# mainboard_rs485_v1_5.net
KiCad netlist of a schematic drawn in Altium Designer
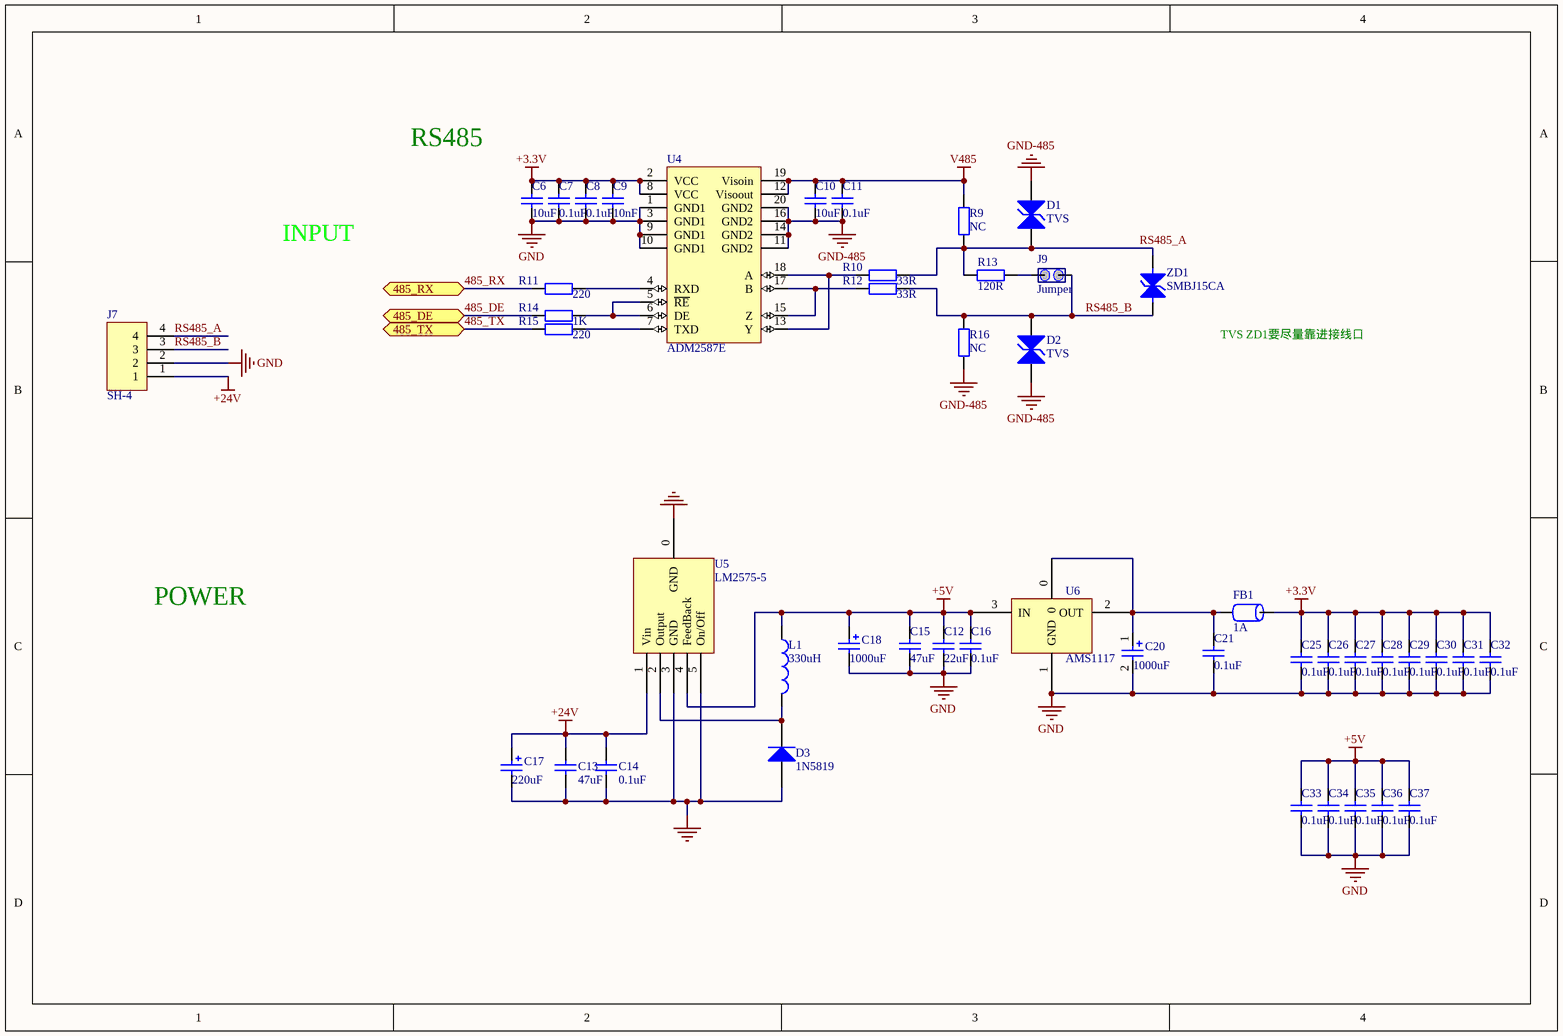
[diagram p0: mainboard_rs485.v1.5.SchDoc]

(export (version "E")
  (design (tool "Eeschema 10.0.6"))
  (components
    (comp (ref "C6")
      (value "10uF")
      (footprint "0805")
      (description "Capacitor")
      (fields (field (name "PUBLISHER") "Altium Limited"))
      (libsource (lib "TIAN's Schlib") (part "Cap"))
    )
    (comp (ref "C7")
      (value "0.1uF")
      (footprint "0805")
      (description "Capacitor")
      (fields (field (name "PUBLISHER") "Altium Limited"))
      (libsource (lib "TIAN's Schlib") (part "Cap"))
    )
    (comp (ref "C8")
      (value "0.1uF")
      (footprint "0805")
      (description "Capacitor")
      (fields (field (name "PUBLISHER") "Altium Limited"))
      (libsource (lib "TIAN's Schlib") (part "Cap"))
    )
    (comp (ref "C9")
      (value "10nF")
      (footprint "0805")
      (description "Capacitor")
      (fields (field (name "PUBLISHER") "Altium Limited"))
      (libsource (lib "TIAN's Schlib") (part "Cap"))
    )
    (comp (ref "C10")
      (value "10uF")
      (footprint "0805")
      (description "Capacitor")
      (fields (field (name "PUBLISHER") "Altium Limited"))
      (libsource (lib "TIAN's Schlib") (part "Cap"))
    )
    (comp (ref "C11")
      (value "0.1uF")
      (footprint "0805")
      (description "Capacitor")
      (fields (field (name "PUBLISHER") "Altium Limited"))
      (libsource (lib "TIAN's Schlib") (part "Cap"))
    )
    (comp (ref "C12") (value "22uF") (footprint "1206") (libsource (lib "Componet") (part "Cap0805")))
    (comp (ref "C13")
      (value "47uF")
      (footprint "1812")
      (description "Capacitor")
      (fields (field (name "PUBLISHER") "Altium Limited"))
      (libsource (lib "Miscellaneous Devices") (part "Cap"))
    )
    (comp (ref "C14")
      (value "0.1uF")
      (footprint "0805")
      (description "Capacitor")
      (fields (field (name "PUBLISHER") "Altium Limited"))
      (libsource (lib "Miscellaneous Devices") (part "Cap"))
    )
    (comp (ref "C15") (value "47uF") (footprint "1812") (libsource (lib "Componet") (part "Cap0805")))
    (comp (ref "C16") (value "0.1uF") (footprint "0805") (libsource (lib "Componet") (part "Cap0805")))
    (comp (ref "C17")
      (value "220uF")
      (footprint "CAP-5mm")
      (description "Polarized Capacitor (Radial)")
      (fields (field (name "PUBLISHER") "Altium Limited"))
      (libsource (lib "Miscellaneous Devices") (part "Cap Pol1"))
    )
    (comp (ref "C18")
      (value "1000uF")
      (footprint "CAP_SMT_10X10")
      (description "Polarized Capacitor (Radial)")
      (fields (field (name "PUBLISHER") "Altium Limited"))
      (libsource (lib "Miscellaneous Devices") (part "Cap Pol1"))
    )
    (comp (ref "C20")
      (value "1000uF")
      (footprint "CAP_SMT_10X10")
      (description "Polarized Capacitor (Radial)")
      (fields (field (name "PUBLISHER") "Altium Limited"))
      (libsource (lib "") (part "Cap Pol1_1"))
    )
    (comp (ref "C21") (value "0.1uF") (footprint "0805") (libsource (lib "Componet") (part "Cap0805")))
    (comp (ref "C25") (value "0.1uF") (footprint "0805") (libsource (lib "Componet") (part "Cap0805")))
    (comp (ref "C26") (value "0.1uF") (footprint "0805") (libsource (lib "Componet") (part "Cap0805")))
    (comp (ref "C27") (value "0.1uF") (footprint "0805") (libsource (lib "Componet") (part "Cap0805")))
    (comp (ref "C28") (value "0.1uF") (footprint "0805") (libsource (lib "Componet") (part "Cap0805")))
    (comp (ref "C29") (value "0.1uF") (footprint "0805") (libsource (lib "Componet") (part "Cap0805")))
    (comp (ref "C30") (value "0.1uF") (footprint "0805") (libsource (lib "Componet") (part "Cap0805")))
    (comp (ref "C31") (value "0.1uF") (footprint "0805") (libsource (lib "Componet") (part "Cap0805")))
    (comp (ref "C32") (value "0.1uF") (footprint "0805") (libsource (lib "Componet") (part "Cap0805")))
    (comp (ref "C33") (value "0.1uF") (footprint "0805") (libsource (lib "Componet") (part "Cap0805")))
    (comp (ref "C34") (value "0.1uF") (footprint "0805") (libsource (lib "Componet") (part "Cap0805")))
    (comp (ref "C35") (value "0.1uF") (footprint "0805") (libsource (lib "Componet") (part "Cap0805")))
    (comp (ref "C36") (value "0.1uF") (footprint "0805") (libsource (lib "Componet") (part "Cap0805")))
    (comp (ref "C37") (value "0.1uF") (footprint "0805") (libsource (lib "Componet") (part "Cap0805")))
    (comp (ref "D1")
      (value "TVS")
      (footprint "SMBJ_DO-214")
      (fields (field (name "PUBLISHER") "Altium Limited"))
      (libsource (lib "TIAN's Schlib") (part "TVS"))
    )
    (comp (ref "D2")
      (value "TVS")
      (footprint "SMBJ_DO-214")
      (fields (field (name "PUBLISHER") "Altium Limited"))
      (libsource (lib "TIAN's Schlib") (part "TVS"))
    )
    (comp (ref "D3")
      (value "1N5819")
      (footprint "Diode_TP2")
      (description "High Conductance Fast Diode")
      (fields (field (name "PUBLISHER") "Altium Limited"))
      (libsource (lib "Miscellaneous Devices") (part "Diode 1N4148"))
    )
    (comp (ref "FB1") (value "1A") (footprint "0805") (libsource (lib "Connector") (part "FERRITE")))
    (comp (ref "J7") (value "SH-4") (footprint "PWR") (libsource (lib "Connector") (part "SH-4")))
    (comp (ref "J9") (value "Jumper") (footprint "J254-2") (libsource (lib "Connector") (part "Jumper")))
    (comp (ref "L1")
      (value "330uH")
      (footprint "Inductance")
      (description "Inductor")
      (fields (field (name "PUBLISHER") "Altium Limited"))
      (libsource (lib "Miscellaneous Devices") (part "Inductor"))
    )
    (comp (ref "R9")
      (value "NC")
      (footprint "0805")
      (description "Resistor")
      (fields (field (name "PUBLISHER") "Altium Limited"))
      (libsource (lib "TIAN's Schlib") (part "Res2"))
    )
    (comp (ref "R10")
      (value "33R")
      (footprint "0805")
      (description "Resistor")
      (fields (field (name "PUBLISHER") "Altium Limited"))
      (libsource (lib "") (part "Res2_2"))
    )
    (comp (ref "R11")
      (value "220")
      (footprint "0805")
      (description "Resistor")
      (fields (field (name "PUBLISHER") "Altium Limited"))
      (libsource (lib "TIAN's Schlib") (part "Res2"))
    )
    (comp (ref "R12")
      (value "33R")
      (footprint "0805")
      (description "Resistor")
      (fields (field (name "PUBLISHER") "Altium Limited"))
      (libsource (lib "") (part "Res2_2"))
    )
    (comp (ref "R13")
      (value "120R")
      (footprint "0805")
      (description "Resistor")
      (fields (field (name "PUBLISHER") "Altium Limited"))
      (libsource (lib "") (part "Res2_1"))
    )
    (comp (ref "R14")
      (value "1K")
      (footprint "0805")
      (description "Resistor")
      (fields (field (name "PUBLISHER") "Altium Limited"))
      (libsource (lib "TIAN's Schlib") (part "Res2"))
    )
    (comp (ref "R15")
      (value "220")
      (footprint "0805")
      (description "Resistor")
      (fields (field (name "PUBLISHER") "Altium Limited"))
      (libsource (lib "TIAN's Schlib") (part "Res2"))
    )
    (comp (ref "R16")
      (value "NC")
      (footprint "0805")
      (description "Resistor")
      (fields (field (name "PUBLISHER") "Altium Limited"))
      (libsource (lib "TIAN's Schlib") (part "Res2"))
    )
    (comp (ref "U4")
      (value "ADM2587E")
      (footprint "SOIC_W_20")
      (description "isolated DC-DC RS485")
      (libsource (lib "TIAN's Schlib") (part "ADM2587E"))
    )
    (comp (ref "U5") (value "LM2575-5") (footprint "TO-263") (libsource (lib "Leon") (part "LM25XX")))
    (comp (ref "U6") (value "AMS1117") (footprint "TO-223") (libsource (lib "Chip") (part "AMS1117")))
    (comp (ref "ZD1")
      (value "SMBJ15CA")
      (footprint "DO-214AA/SMB")
      (description "瞬态抑制二极管")
      (libsource (lib "ALARM") (part "TVS"))
    )
  )
  (nets
    (net (code "1") (name "+3.3V") (class "Default")
      (node (ref "C25") (pin "2") (pinfunction "2_2") (pintype "passive"))
      (node (ref "C26") (pin "2") (pinfunction "2_2") (pintype "passive"))
      (node (ref "C27") (pin "2") (pinfunction "2_2") (pintype "passive"))
      (node (ref "C28") (pin "2") (pinfunction "2_2") (pintype "passive"))
      (node (ref "C29") (pin "2") (pinfunction "2_2") (pintype "passive"))
      (node (ref "C30") (pin "2") (pinfunction "2_2") (pintype "passive"))
      (node (ref "C31") (pin "2") (pinfunction "2_2") (pintype "passive"))
      (node (ref "C32") (pin "2") (pinfunction "2_2") (pintype "passive"))
      (node (ref "C6") (pin "2") (pinfunction "2_2") (pintype "passive"))
      (node (ref "C7") (pin "2") (pinfunction "2_2") (pintype "passive"))
      (node (ref "C8") (pin "2") (pinfunction "2_2") (pintype "passive"))
      (node (ref "C9") (pin "2") (pinfunction "2_2") (pintype "passive"))
      (node (ref "FB1") (pin "2") (pinfunction "2_2") (pintype "passive"))
      (node (ref "U4") (pin "2") (pinfunction "VCC_2") (pintype "passive"))
      (node (ref "U4") (pin "8") (pinfunction "VCC_8") (pintype "passive"))
    )
    (net (code "2") (name "+5V") (class "Default")
      (node (ref "C12") (pin "2") (pinfunction "2_2") (pintype "passive"))
      (node (ref "C15") (pin "2") (pinfunction "2_2") (pintype "passive"))
      (node (ref "C16") (pin "2") (pinfunction "2_2") (pintype "passive"))
      (node (ref "C18") (pin "1") (pinfunction "1_1") (pintype "passive"))
      (node (ref "C33") (pin "2") (pinfunction "2_2") (pintype "passive"))
      (node (ref "C34") (pin "2") (pinfunction "2_2") (pintype "passive"))
      (node (ref "C35") (pin "2") (pinfunction "2_2") (pintype "passive"))
      (node (ref "C36") (pin "2") (pinfunction "2_2") (pintype "passive"))
      (node (ref "C37") (pin "2") (pinfunction "2_2") (pintype "passive"))
      (node (ref "L1") (pin "1") (pinfunction "1_1") (pintype "passive"))
      (node (ref "U5") (pin "4") (pinfunction "FeedBack_4") (pintype "passive"))
      (node (ref "U6") (pin "3") (pinfunction "IN_3") (pintype "passive"))
    )
    (net (code "3") (name "+24V") (class "Default")
      (node (ref "C13") (pin "2") (pinfunction "2_2") (pintype "passive"))
      (node (ref "C14") (pin "2") (pinfunction "2_2") (pintype "passive"))
      (node (ref "C17") (pin "1") (pinfunction "1_1") (pintype "passive"))
      (node (ref "J7") (pin "1") (pinfunction "1_1") (pintype "passive"))
      (node (ref "U5") (pin "1") (pinfunction "Vin_1") (pintype "passive"))
    )
    (net (code "4") (name "/485_DE") (class "Default")
      (node (ref "R14") (pin "1") (pinfunction "1_1") (pintype "passive"))
    )
    (net (code "5") (name "/485_RX") (class "Default")
      (node (ref "R11") (pin "1") (pinfunction "1_1") (pintype "passive"))
    )
    (net (code "6") (name "/485_TX") (class "Default")
      (node (ref "R15") (pin "1") (pinfunction "1_1") (pintype "passive"))
    )
    (net (code "7") (name "/RS485_A") (class "Default")
      (node (ref "D1") (pin "2") (pinfunction "K_2") (pintype "passive"))
      (node (ref "J7") (pin "4") (pinfunction "4_4") (pintype "passive"))
      (node (ref "R10") (pin "2") (pinfunction "2_2") (pintype "passive"))
      (node (ref "R13") (pin "2") (pinfunction "2_2") (pintype "passive"))
      (node (ref "R9") (pin "1") (pinfunction "1_1") (pintype "passive"))
      (node (ref "ZD1") (pin "1") (pinfunction "1_1") (pintype "passive"))
    )
    (net (code "8") (name "/RS485_B") (class "Default")
      (node (ref "D2") (pin "2") (pinfunction "K_2") (pintype "passive"))
      (node (ref "J7") (pin "3") (pinfunction "3_3") (pintype "passive"))
      (node (ref "J9") (pin "1") (pinfunction "1_1") (pintype "passive"))
      (node (ref "R12") (pin "2") (pinfunction "2_2") (pintype "passive"))
      (node (ref "R16") (pin "2") (pinfunction "2_2") (pintype "passive"))
      (node (ref "ZD1") (pin "2") (pinfunction "2_2") (pintype "passive"))
    )
    (net (code "9") (name "GND") (class "Default")
      (node (ref "C12") (pin "1") (pinfunction "1_1") (pintype "passive"))
      (node (ref "C13") (pin "1") (pinfunction "1_1") (pintype "passive"))
      (node (ref "C14") (pin "1") (pinfunction "1_1") (pintype "passive"))
      (node (ref "C15") (pin "1") (pinfunction "1_1") (pintype "passive"))
      (node (ref "C16") (pin "1") (pinfunction "1_1") (pintype "passive"))
      (node (ref "C17") (pin "2") (pinfunction "2_2") (pintype "passive"))
      (node (ref "C18") (pin "2") (pinfunction "2_2") (pintype "passive"))
      (node (ref "C20") (pin "2") (pinfunction "2_2") (pintype "passive"))
      (node (ref "C21") (pin "1") (pinfunction "1_1") (pintype "passive"))
      (node (ref "C25") (pin "1") (pinfunction "1_1") (pintype "passive"))
      (node (ref "C26") (pin "1") (pinfunction "1_1") (pintype "passive"))
      (node (ref "C27") (pin "1") (pinfunction "1_1") (pintype "passive"))
      (node (ref "C28") (pin "1") (pinfunction "1_1") (pintype "passive"))
      (node (ref "C29") (pin "1") (pinfunction "1_1") (pintype "passive"))
      (node (ref "C30") (pin "1") (pinfunction "1_1") (pintype "passive"))
      (node (ref "C31") (pin "1") (pinfunction "1_1") (pintype "passive"))
      (node (ref "C32") (pin "1") (pinfunction "1_1") (pintype "passive"))
      (node (ref "C33") (pin "1") (pinfunction "1_1") (pintype "passive"))
      (node (ref "C34") (pin "1") (pinfunction "1_1") (pintype "passive"))
      (node (ref "C35") (pin "1") (pinfunction "1_1") (pintype "passive"))
      (node (ref "C36") (pin "1") (pinfunction "1_1") (pintype "passive"))
      (node (ref "C37") (pin "1") (pinfunction "1_1") (pintype "passive"))
      (node (ref "C6") (pin "1") (pinfunction "1_1") (pintype "passive"))
      (node (ref "C7") (pin "1") (pinfunction "1_1") (pintype "passive"))
      (node (ref "C8") (pin "1") (pinfunction "1_1") (pintype "passive"))
      (node (ref "C9") (pin "1") (pinfunction "1_1") (pintype "passive"))
      (node (ref "D3") (pin "1") (pinfunction "A_1") (pintype "passive"))
      (node (ref "J7") (pin "2") (pinfunction "2_2") (pintype "passive"))
      (node (ref "U4") (pin "1") (pinfunction "GND1_1") (pintype "passive"))
      (node (ref "U4") (pin "10") (pinfunction "GND1_10") (pintype "passive"))
      (node (ref "U4") (pin "3") (pinfunction "GND1_3") (pintype "passive"))
      (node (ref "U4") (pin "9") (pinfunction "GND1_9") (pintype "passive"))
      (node (ref "U5") (pin "0") (pinfunction "GND_0") (pintype "passive"))
      (node (ref "U5") (pin "3") (pinfunction "GND_3") (pintype "passive"))
      (node (ref "U5") (pin "5") (pinfunction "On/Off_5") (pintype "passive"))
      (node (ref "U6") (pin "1") (pinfunction "GND_1") (pintype "passive"))
    )
    (net (code "10") (name "GND-485") (class "Default")
      (node (ref "C10") (pin "1") (pinfunction "1_1") (pintype "passive"))
      (node (ref "C11") (pin "1") (pinfunction "1_1") (pintype "passive"))
      (node (ref "D1") (pin "1") (pinfunction "A_1") (pintype "passive"))
      (node (ref "D2") (pin "1") (pinfunction "A_1") (pintype "passive"))
      (node (ref "R16") (pin "1") (pinfunction "1_1") (pintype "passive"))
      (node (ref "U4") (pin "11") (pinfunction "GND2_11") (pintype "passive"))
      (node (ref "U4") (pin "14") (pinfunction "GND2_14") (pintype "passive"))
      (node (ref "U4") (pin "16") (pinfunction "GND2_16") (pintype "passive"))
      (node (ref "U4") (pin "20") (pinfunction "GND2_20") (pintype "passive"))
    )
    (net (code "11") (name "Net-(D3-K)") (class "Default")
      (node (ref "D3") (pin "2") (pinfunction "K_2") (pintype "passive"))
      (node (ref "L1") (pin "2") (pinfunction "2_2") (pintype "passive"))
      (node (ref "U5") (pin "2") (pinfunction "Output_2") (pintype "passive"))
    )
    (net (code "12") (name "Net-(J9-Pad2)") (class "Default")
      (node (ref "J9") (pin "2") (pinfunction "2_2") (pintype "passive"))
      (node (ref "R13") (pin "1") (pinfunction "1_1") (pintype "passive"))
    )
    (net (code "13") (name "Net-(U4-A)") (class "Default")
      (node (ref "R10") (pin "1") (pinfunction "1_1") (pintype "passive"))
      (node (ref "U4") (pin "13") (pinfunction "Y_13") (pintype "bidirectional"))
      (node (ref "U4") (pin "18") (pinfunction "A_18") (pintype "bidirectional"))
    )
    (net (code "14") (name "Net-(U4-B)") (class "Default")
      (node (ref "R12") (pin "1") (pinfunction "1_1") (pintype "passive"))
      (node (ref "U4") (pin "15") (pinfunction "Z_15") (pintype "bidirectional"))
      (node (ref "U4") (pin "17") (pinfunction "B_17") (pintype "bidirectional"))
    )
    (net (code "15") (name "Net-(U4-DE)") (class "Default")
      (node (ref "R14") (pin "2") (pinfunction "2_2") (pintype "passive"))
      (node (ref "U4") (pin "5") (pinfunction "~{RE}_5") (pintype "bidirectional"))
      (node (ref "U4") (pin "6") (pinfunction "DE_6") (pintype "bidirectional"))
    )
    (net (code "16") (name "Net-(U4-RXD)") (class "Default")
      (node (ref "R11") (pin "2") (pinfunction "2_2") (pintype "passive"))
      (node (ref "U4") (pin "4") (pinfunction "RXD_4") (pintype "bidirectional"))
    )
    (net (code "17") (name "Net-(U4-TXD)") (class "Default")
      (node (ref "R15") (pin "2") (pinfunction "2_2") (pintype "passive"))
      (node (ref "U4") (pin "7") (pinfunction "TXD_7") (pintype "bidirectional"))
    )
    (net (code "18") (name "Net-(U6-OUT)") (class "Default")
      (node (ref "C20") (pin "1") (pinfunction "1_1") (pintype "passive"))
      (node (ref "C21") (pin "2") (pinfunction "2_2") (pintype "passive"))
      (node (ref "FB1") (pin "1") (pinfunction "1_1") (pintype "passive"))
      (node (ref "U6") (pin "0") (pinfunction "0_0") (pintype "passive"))
      (node (ref "U6") (pin "2") (pinfunction "OUT_2") (pintype "passive"))
    )
    (net (code "19") (name "V485") (class "Default")
      (node (ref "C10") (pin "2") (pinfunction "2_2") (pintype "passive"))
      (node (ref "C11") (pin "2") (pinfunction "2_2") (pintype "passive"))
      (node (ref "R9") (pin "2") (pinfunction "2_2") (pintype "passive"))
      (node (ref "U4") (pin "12") (pinfunction "Visoout_12") (pintype "passive"))
      (node (ref "U4") (pin "19") (pinfunction "Visoin_19") (pintype "passive"))
    )
  )
)
